# V_4.net
KiCad netlist of a schematic drawn in Altium Designer
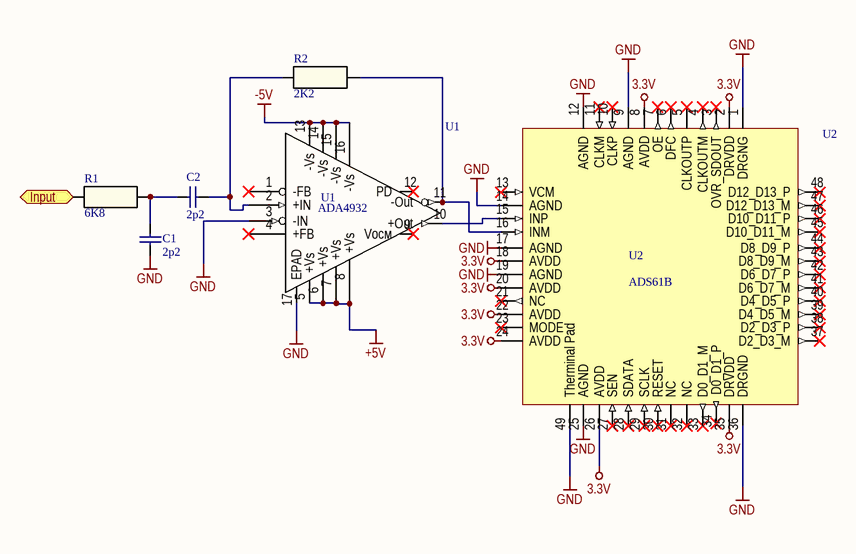
[diagram p0: V_4.SchDoc]

(export (version "E")
  (design (tool "Eeschema 10.0.6"))
  (components
    (comp (ref "C1") (value "2p2") (footprint "Cap0805") (libsource (lib "V_4") (part "Capacitor")))
    (comp (ref "C2") (value "2p2") (footprint "Cap0805") (libsource (lib "V_4") (part "Capacitor")))
    (comp (ref "R1") (value "6K8") (footprint "Res0805") (libsource (lib "V_4") (part "Resistor")))
    (comp (ref "R2") (value "2K2") (footprint "Res0805") (libsource (lib "V_4") (part "Resistor")))
    (comp (ref "U1") (value "ADA4932") (footprint "ADA4932") (libsource (lib "V_4") (part "ADA4932")))
    (comp (ref "U2") (value "ADS61B49") (footprint "ADS61B49") (libsource (lib "V_4") (part "ADS61B49")))
  )
  (nets
    (net (code "1") (name "+5V") (class "Default")
      (node (ref "U1") (pin "5") (pinfunction "+Vs_5") (pintype "power_in"))
      (node (ref "U1") (pin "6") (pinfunction "+Vs_6") (pintype "power_in"))
      (node (ref "U1") (pin "7") (pinfunction "+Vs_7") (pintype "power_in"))
      (node (ref "U1") (pin "8") (pinfunction "+Vs_8") (pintype "power_in"))
    )
    (net (code "2") (name "-5V") (class "Default")
      (node (ref "U1") (pin "13") (pinfunction "-Vs_13") (pintype "power_in"))
      (node (ref "U1") (pin "14") (pinfunction "-Vs_14") (pintype "power_in"))
      (node (ref "U1") (pin "15") (pinfunction "-Vs_15") (pintype "power_in"))
      (node (ref "U1") (pin "16") (pinfunction "-Vs_16") (pintype "power_in"))
    )
    (net (code "3") (name "/Input") (class "Default") (node (ref "R1") (pin "1") (pintype "passive")))
    (net (code "4") (name "3.3V") (class "Default")
      (node (ref "U2") (pin "18") (pinfunction "AVDD_18") (pintype "power_in"))
      (node (ref "U2") (pin "2") (pinfunction "DRVDD_2") (pintype "power_in"))
      (node (ref "U2") (pin "20") (pinfunction "AVDD_20") (pintype "power_in"))
      (node (ref "U2") (pin "22") (pinfunction "AVDD_22") (pintype "power_in"))
      (node (ref "U2") (pin "24") (pinfunction "AVDD_24") (pintype "power_in"))
      (node (ref "U2") (pin "26") (pinfunction "AVDD_26") (pintype "power_in"))
      (node (ref "U2") (pin "35") (pinfunction "DRVDD_35") (pintype "passive"))
      (node (ref "U2") (pin "8") (pinfunction "AVDD_8") (pintype "power_in"))
    )
    (net (code "5") (name "GND") (class "Default")
      (node (ref "C1") (pin "1") (pintype "passive"))
      (node (ref "U1") (pin "17") (pinfunction "EPAD_17") (pintype "power_in"))
      (node (ref "U1") (pin "3") (pinfunction "-IN_3") (pintype "input"))
      (node (ref "U2") (pin "1") (pinfunction "DRGNG_1") (pintype "power_in"))
      (node (ref "U2") (pin "12") (pinfunction "AGND_12") (pintype "power_in"))
      (node (ref "U2") (pin "14") (pinfunction "AGND_14") (pintype "power_in"))
      (node (ref "U2") (pin "17") (pinfunction "AGND_17") (pintype "power_in"))
      (node (ref "U2") (pin "19") (pinfunction "AGND_19") (pintype "power_in"))
      (node (ref "U2") (pin "25") (pinfunction "AGND_25") (pintype "power_in"))
      (node (ref "U2") (pin "36") (pinfunction "DRGND_36") (pintype "passive"))
      (node (ref "U2") (pin "49") (pinfunction "Therminal_Pad_49") (pintype "power_in"))
      (node (ref "U2") (pin "9") (pinfunction "AGND_9") (pintype "power_in"))
    )
    (net (code "6") (name "Net-(C1-5)") (class "Default")
      (node (ref "C1") (pin "2") (pinfunction "5_2") (pintype "passive"))
      (node (ref "C2") (pin "1") (pintype "passive"))
      (node (ref "R1") (pin "2") (pintype "passive"))
    )
    (net (code "7") (name "Net-(C2-5)") (class "Default")
      (node (ref "C2") (pin "2") (pinfunction "5_2") (pintype "passive"))
      (node (ref "R2") (pin "1") (pintype "passive"))
      (node (ref "U1") (pin "2") (pinfunction "+IN_2") (pintype "input"))
    )
    (net (code "8") (name "Net-(U1-+Out)") (class "Default")
      (node (ref "U1") (pin "10") (pinfunction "+Out_10") (pintype "output"))
      (node (ref "U2") (pin "15") (pinfunction "INP_15") (pintype "input"))
    )
    (net (code "9") (name "Net-(U1--Out)") (class "Default")
      (node (ref "R2") (pin "2") (pintype "passive"))
      (node (ref "U1") (pin "11") (pinfunction "-Out_11") (pintype "output"))
      (node (ref "U2") (pin "16") (pinfunction "INM_16") (pintype "input"))
    )
    (net (code "10") (name "unconnected-(U1-+FB-Pad4)") (class "Default")
      (node (ref "U1") (pin "4") (pinfunction "+FB_4") (pintype "passive+no_connect"))
    )
    (net (code "11") (name "unconnected-(U1--FB-Pad1)") (class "Default")
      (node (ref "U1") (pin "1") (pinfunction "-FB_1") (pintype "passive+no_connect"))
    )
    (net (code "12") (name "unconnected-(U1-PD-Pad12)") (class "Default")
      (node (ref "U1") (pin "12") (pinfunction "PD_12") (pintype "passive+no_connect"))
    )
    (net (code "13") (name "unconnected-(U1-Vосм-Pad9)") (class "Default")
      (node (ref "U1") (pin "9") (pinfunction "Vосм_9") (pintype "power_in+no_connect"))
    )
    (net (code "14") (name "unconnected-(U2-CLKM-Pad11)") (class "Default")
      (node (ref "U2") (pin "11") (pinfunction "CLKM_11") (pintype "input+no_connect"))
    )
    (net (code "15") (name "unconnected-(U2-CLKOUTM-Pad4)") (class "Default")
      (node (ref "U2") (pin "4") (pinfunction "CLKOUTM_4") (pintype "output+no_connect"))
    )
    (net (code "16") (name "unconnected-(U2-CLKOUTP-Pad5)") (class "Default")
      (node (ref "U2") (pin "5") (pinfunction "CLKOUTP_5") (pintype "power_in+no_connect"))
    )
    (net (code "17") (name "unconnected-(U2-CLKP-Pad10)") (class "Default")
      (node (ref "U2") (pin "10") (pinfunction "CLKP_10") (pintype "input+no_connect"))
    )
    (net (code "18") (name "unconnected-(U2-D0_D1_M-Pad33)") (class "Default")
      (node (ref "U2") (pin "33") (pinfunction "D0_D1_M_33") (pintype "output+no_connect"))
    )
    (net (code "19") (name "unconnected-(U2-D0_D1_P-Pad34)") (class "Default")
      (node (ref "U2") (pin "34") (pinfunction "D0_D1_P_34") (pintype "output+no_connect"))
    )
    (net (code "20") (name "unconnected-(U2-D2_D3_M-Pad37)") (class "Default")
      (node (ref "U2") (pin "37") (pinfunction "D2_D3_M_37") (pintype "output+no_connect"))
    )
    (net (code "21") (name "unconnected-(U2-D2_D3_P-Pad38)") (class "Default")
      (node (ref "U2") (pin "38") (pinfunction "D2_D3_P_38") (pintype "output+no_connect"))
    )
    (net (code "22") (name "unconnected-(U2-D4_D5_M-Pad39)") (class "Default")
      (node (ref "U2") (pin "39") (pinfunction "D4_D5_M_39") (pintype "output+no_connect"))
    )
    (net (code "23") (name "unconnected-(U2-D4_D5_P-Pad40)") (class "Default")
      (node (ref "U2") (pin "40") (pinfunction "D4_D5_P_40") (pintype "output+no_connect"))
    )
    (net (code "24") (name "unconnected-(U2-D6_D7_M-Pad41)") (class "Default")
      (node (ref "U2") (pin "41") (pinfunction "D6_D7_M_41") (pintype "output+no_connect"))
    )
    (net (code "25") (name "unconnected-(U2-D6_D7_P-Pad42)") (class "Default")
      (node (ref "U2") (pin "42") (pinfunction "D6_D7_P_42") (pintype "output+no_connect"))
    )
    (net (code "26") (name "unconnected-(U2-D8_D9_M-Pad43)") (class "Default")
      (node (ref "U2") (pin "43") (pinfunction "D8_D9_M_43") (pintype "output+no_connect"))
    )
    (net (code "27") (name "unconnected-(U2-D8_D9_P-Pad44)") (class "Default")
      (node (ref "U2") (pin "44") (pinfunction "D8_D9_P_44") (pintype "output+no_connect"))
    )
    (net (code "28") (name "unconnected-(U2-D10_D11_M-Pad45)") (class "Default")
      (node (ref "U2") (pin "45") (pinfunction "D10_D11_M_45") (pintype "output+no_connect"))
    )
    (net (code "29") (name "unconnected-(U2-D10_D11_P-Pad46)") (class "Default")
      (node (ref "U2") (pin "46") (pinfunction "D10_D11_P_46") (pintype "output+no_connect"))
    )
    (net (code "30") (name "unconnected-(U2-D12_D13_M-Pad47)") (class "Default")
      (node (ref "U2") (pin "47") (pinfunction "D12_D13_M_47") (pintype "output+no_connect"))
    )
    (net (code "31") (name "unconnected-(U2-D12_D13_P-Pad48)") (class "Default")
      (node (ref "U2") (pin "48") (pinfunction "D12_D13_P_48") (pintype "output+no_connect"))
    )
    (net (code "32") (name "unconnected-(U2-DFC-Pad6)") (class "Default")
      (node (ref "U2") (pin "6") (pinfunction "DFC_6") (pintype "output+no_connect"))
    )
    (net (code "33") (name "unconnected-(U2-MODE-Pad23)") (class "Default")
      (node (ref "U2") (pin "23") (pinfunction "MODE_23") (pintype "passive+no_connect"))
    )
    (net (code "34") (name "unconnected-(U2-NC-Pad21)") (class "Default")
      (node (ref "U2") (pin "21") (pinfunction "NC_21") (pintype "output+no_connect"))
    )
    (net (code "35") (name "unconnected-(U2-NC-Pad31)") (class "Default")
      (node (ref "U2") (pin "31") (pinfunction "NC_31") (pintype "passive+no_connect"))
    )
    (net (code "36") (name "unconnected-(U2-NC-Pad32)") (class "Default")
      (node (ref "U2") (pin "32") (pinfunction "NC_32") (pintype "passive+no_connect"))
    )
    (net (code "37") (name "unconnected-(U2-OE-Pad7)") (class "Default")
      (node (ref "U2") (pin "7") (pinfunction "OE_7") (pintype "output+no_connect"))
    )
    (net (code "38") (name "unconnected-(U2-OVR_SDOUT-Pad3)") (class "Default")
      (node (ref "U2") (pin "3") (pinfunction "OVR_SDOUT_3") (pintype "output+no_connect"))
    )
    (net (code "39") (name "unconnected-(U2-RESET-Pad30)") (class "Default")
      (node (ref "U2") (pin "30") (pinfunction "RESET_30") (pintype "input+no_connect"))
    )
    (net (code "40") (name "unconnected-(U2-SCLK-Pad29)") (class "Default")
      (node (ref "U2") (pin "29") (pinfunction "SCLK_29") (pintype "input+no_connect"))
    )
    (net (code "41") (name "unconnected-(U2-SDATA-Pad28)") (class "Default")
      (node (ref "U2") (pin "28") (pinfunction "SDATA_28") (pintype "input+no_connect"))
    )
    (net (code "42") (name "unconnected-(U2-SEN-Pad27)") (class "Default")
      (node (ref "U2") (pin "27") (pinfunction "SEN_27") (pintype "input+no_connect"))
    )
    (net (code "43") (name "unconnected-(U2-VCM-Pad13)") (class "Default")
      (node (ref "U2") (pin "13") (pinfunction "VCM_13") (pintype "input+no_connect"))
    )
  )
)
